# Nikon_PowerBoardV1.net
KiCad netlist of a schematic drawn in EAGLE
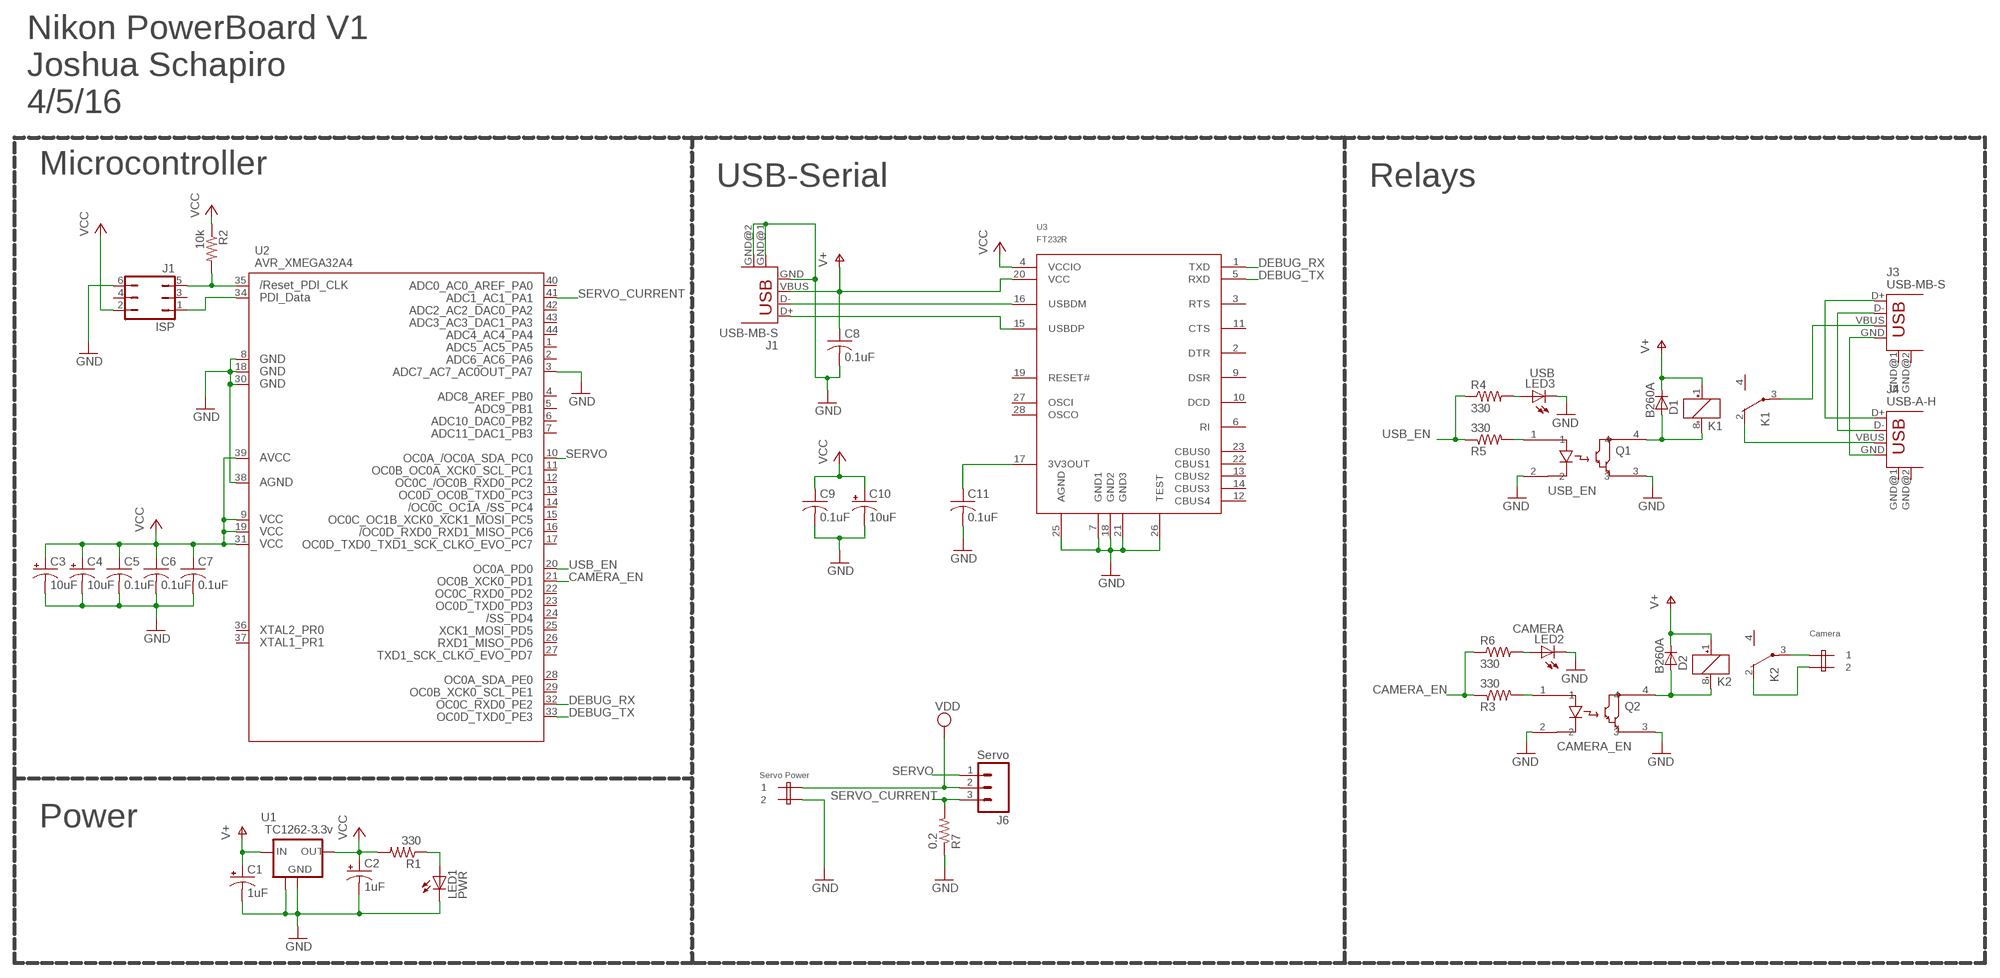
[diagram p0: schematic, sheet 1]

(export (version "E")
  (design (tool "Eeschema 10.0.6"))
  (components
    (comp (ref "C1")
      (value "1uF")
      (footprint "eagle-import:EIA3216")
      (libsource (lib "eagle-import") (part "CAP_POL1206"))
    )
    (comp (ref "C2")
      (value "1uF")
      (footprint "eagle-import:EIA3216")
      (libsource (lib "eagle-import") (part "CAP_POL1206"))
    )
    (comp (ref "C3")
      (value "10uF")
      (footprint "eagle-import:EIA3216")
      (libsource (lib "eagle-import") (part "CAP_POL1206"))
    )
    (comp (ref "C4")
      (value "10uF")
      (footprint "eagle-import:EIA3216")
      (libsource (lib "eagle-import") (part "CAP_POL1206"))
    )
    (comp (ref "C5")
      (value "0.1uF")
      (footprint "eagle-import:C1206")
      (libsource (lib "eagle-import") (part "C-USC1206"))
    )
    (comp (ref "C6")
      (value "0.1uF")
      (footprint "eagle-import:C1206")
      (libsource (lib "eagle-import") (part "C-USC1206"))
    )
    (comp (ref "C7")
      (value "0.1uF")
      (footprint "eagle-import:C1206")
      (libsource (lib "eagle-import") (part "C-USC1206"))
    )
    (comp (ref "C8")
      (value "0.1uF")
      (footprint "eagle-import:C1206")
      (libsource (lib "eagle-import") (part "C-USC1206"))
    )
    (comp (ref "C9")
      (value "0.1uF")
      (footprint "eagle-import:C1206")
      (libsource (lib "eagle-import") (part "C-USC1206"))
    )
    (comp (ref "C10")
      (value "10uF")
      (footprint "eagle-import:EIA3216")
      (libsource (lib "eagle-import") (part "CAP_POL1206"))
    )
    (comp (ref "C11")
      (value "0.1uF")
      (footprint "eagle-import:C1206")
      (libsource (lib "eagle-import") (part "C-USC1206"))
    )
    (comp (ref "D1")
      (value "B260A")
      (footprint "eagle-import:SMA-DIODE")
      (libsource (lib "eagle-import") (part "DIODESMA"))
    )
    (comp (ref "D2")
      (value "B260A")
      (footprint "eagle-import:SMA-DIODE")
      (libsource (lib "eagle-import") (part "DIODESMA"))
    )
    (comp (ref "ISP")
      (value "J1")
      (footprint "eagle-import:JP3Q")
      (libsource (lib "eagle-import") (part "JP3Q"))
    )
    (comp (ref "J1")
      (value "USB-MB-S")
      (footprint "eagle-import:USB-MB-S")
      (libsource (lib "eagle-import") (part "USB-MB-S"))
    )
    (comp (ref "J2")
      (value "Camera")
      (footprint "eagle-import:2-PIN_SCREWTERM")
      (libsource (lib "eagle-import") (part "2-PIN_SCREWTERMINAL"))
    )
    (comp (ref "J3")
      (value "USB-MB-S")
      (footprint "eagle-import:USB-MB-S")
      (libsource (lib "eagle-import") (part "USB-MB-S"))
    )
    (comp (ref "J4")
      (value "USB-A-H")
      (footprint "eagle-import:USB-A-H")
      (libsource (lib "eagle-import") (part "USB-A-H"))
    )
    (comp (ref "J5")
      (value "ServoPower")
      (footprint "eagle-import:2-PIN_SCREWTERM")
      (libsource (lib "eagle-import") (part "2-PIN_SCREWTERMINAL"))
    )
    (comp (ref "J6")
      (value "Servo")
      (footprint "eagle-import:1X03_LONGPADS")
      (libsource (lib "eagle-import") (part "M03LONGPADS"))
    )
    (comp (ref "K1")
      (value "USB_EN")
      (footprint "eagle-import:G6K-2F")
      (libsource (lib "eagle-import") (part "G6K-2F"))
    )
    (comp (ref "K2")
      (value "CAMERA_EN")
      (footprint "eagle-import:G6K-2F")
      (libsource (lib "eagle-import") (part "G6K-2F"))
    )
    (comp (ref "LED1")
      (value "PWR")
      (footprint "eagle-import:CHIPLED_1206")
      (libsource (lib "eagle-import") (part "LEDCHIPLED_1206"))
    )
    (comp (ref "LED2")
      (value "CAMERA")
      (footprint "eagle-import:CHIPLED_1206")
      (libsource (lib "eagle-import") (part "LEDCHIPLED_1206"))
    )
    (comp (ref "LED3")
      (value "USB")
      (footprint "eagle-import:CHIPLED_1206")
      (libsource (lib "eagle-import") (part "LEDCHIPLED_1206"))
    )
    (comp (ref "Q1")
      (value "USB_EN")
      (footprint "eagle-import:4-PIN_MINI-FLAT")
      (libsource (lib "eagle-import") (part "OPTOISOLATOR_SINGLE"))
    )
    (comp (ref "Q2")
      (value "CAMERA_EN")
      (footprint "eagle-import:4-PIN_MINI-FLAT")
      (libsource (lib "eagle-import") (part "OPTOISOLATOR_SINGLE"))
    )
    (comp (ref "R1")
      (value "330")
      (footprint "eagle-import:R1206")
      (libsource (lib "eagle-import") (part "R-US_R1206"))
    )
    (comp (ref "R2")
      (value "10k")
      (footprint "eagle-import:R1206")
      (libsource (lib "eagle-import") (part "R-US_R1206"))
    )
    (comp (ref "R3")
      (value "330")
      (footprint "eagle-import:R1206")
      (libsource (lib "eagle-import") (part "R-US_R1206"))
    )
    (comp (ref "R4")
      (value "330")
      (footprint "eagle-import:R1206")
      (libsource (lib "eagle-import") (part "R-US_R1206"))
    )
    (comp (ref "R5")
      (value "330")
      (footprint "eagle-import:R1206")
      (libsource (lib "eagle-import") (part "R-US_R1206"))
    )
    (comp (ref "R6")
      (value "330")
      (footprint "eagle-import:R1206")
      (libsource (lib "eagle-import") (part "R-US_R1206"))
    )
    (comp (ref "R7")
      (value "0.2")
      (footprint "eagle-import:R1206")
      (libsource (lib "eagle-import") (part "R-US_R1206"))
    )
    (comp (ref "U1")
      (value "TC1262-3.3v")
      (footprint "eagle-import:SOT223")
      (libsource (lib "eagle-import") (part "REGULATOR"))
    )
    (comp (ref "U2")
      (value "AVR_XMEGA32A4")
      (footprint "eagle-import:TQFP44")
      (libsource (lib "eagle-import") (part "AVR_XMEGA_A4_44A"))
    )
    (comp (ref "U3")
      (value "FT232R")
      (footprint "eagle-import:SSOP28")
      (libsource (lib "eagle-import") (part "FT232R"))
    )
  )
  (nets
    (net (code "1") (name "/CAMERA_EN") (class "Default")
      (node (ref "R3") (pin "1") (pinfunction "1_1") (pintype "passive"))
      (node (ref "R6") (pin "1") (pinfunction "1_1") (pintype "passive"))
      (node (ref "U2") (pin "21") (pinfunction "PD1_21") (pintype "bidirectional"))
    )
    (net (code "2") (name "/DEBUG_RX") (class "Default")
      (node (ref "U2") (pin "32") (pinfunction "PE2_32") (pintype "bidirectional"))
      (node (ref "U3") (pin "1") (pinfunction "TXD_1") (pintype "bidirectional"))
    )
    (net (code "3") (name "/DEBUG_TX") (class "Default")
      (node (ref "U2") (pin "33") (pinfunction "PE3_33") (pintype "bidirectional"))
      (node (ref "U3") (pin "5") (pinfunction "RXD_5") (pintype "bidirectional"))
    )
    (net (code "4") (name "/SERVO") (class "Default")
      (node (ref "J6") (pin "1") (pinfunction "1_1") (pintype "passive"))
      (node (ref "U2") (pin "10") (pinfunction "PC0_10") (pintype "bidirectional"))
    )
    (net (code "5") (name "/SERVO_CURRENT") (class "Default")
      (node (ref "J6") (pin "3") (pinfunction "3_3") (pintype "passive"))
      (node (ref "R7") (pin "2") (pinfunction "2_2") (pintype "passive"))
      (node (ref "U2") (pin "41") (pinfunction "PA1_41") (pintype "bidirectional"))
    )
    (net (code "6") (name "/USB_EN") (class "Default")
      (node (ref "R4") (pin "1") (pinfunction "1_1") (pintype "passive"))
      (node (ref "R5") (pin "1") (pinfunction "1_1") (pintype "passive"))
      (node (ref "U2") (pin "20") (pinfunction "PD0_20") (pintype "bidirectional"))
    )
    (net (code "7") (name "GND") (class "Default")
      (node (ref "C1") (pin "C") (pinfunction "-_C") (pintype "passive"))
      (node (ref "C10") (pin "C") (pinfunction "-_C") (pintype "passive"))
      (node (ref "C11") (pin "2") (pinfunction "2_2") (pintype "passive"))
      (node (ref "C2") (pin "C") (pinfunction "-_C") (pintype "passive"))
      (node (ref "C3") (pin "C") (pinfunction "-_C") (pintype "passive"))
      (node (ref "C4") (pin "C") (pinfunction "-_C") (pintype "passive"))
      (node (ref "C5") (pin "2") (pinfunction "2_2") (pintype "passive"))
      (node (ref "C6") (pin "2") (pinfunction "2_2") (pintype "passive"))
      (node (ref "C7") (pin "2") (pinfunction "2_2") (pintype "passive"))
      (node (ref "C8") (pin "2") (pinfunction "2_2") (pintype "passive"))
      (node (ref "C9") (pin "2") (pinfunction "2_2") (pintype "passive"))
      (node (ref "ISP") (pin "6") (pinfunction "6_6") (pintype "passive"))
      (node (ref "J1") (pin "GND") (pinfunction "GND_GND") (pintype "bidirectional"))
      (node (ref "J1") (pin "GND@1") (pinfunction "GND_GND@1") (pintype "bidirectional"))
      (node (ref "J1") (pin "GND@2") (pinfunction "GND_GND@2") (pintype "bidirectional"))
      (node (ref "J5") (pin "P$2") (pinfunction "2_P$2") (pintype "bidirectional"))
      (node (ref "LED1") (pin "C") (pinfunction "C_C") (pintype "passive"))
      (node (ref "LED2") (pin "C") (pinfunction "C_C") (pintype "passive"))
      (node (ref "LED3") (pin "C") (pinfunction "C_C") (pintype "passive"))
      (node (ref "Q1") (pin "2") (pinfunction "2_2") (pintype "bidirectional"))
      (node (ref "Q1") (pin "3") (pinfunction "3_3") (pintype "bidirectional"))
      (node (ref "Q2") (pin "2") (pinfunction "2_2") (pintype "bidirectional"))
      (node (ref "Q2") (pin "3") (pinfunction "3_3") (pintype "bidirectional"))
      (node (ref "R7") (pin "1") (pinfunction "1_1") (pintype "passive"))
      (node (ref "U1") (pin "2") (pinfunction "GND_2") (pintype "bidirectional"))
      (node (ref "U1") (pin "4") (pinfunction "GND1_4") (pintype "bidirectional"))
      (node (ref "U2") (pin "18") (pinfunction "GND2_18") (pintype "bidirectional"))
      (node (ref "U2") (pin "3") (pinfunction "PA7_3") (pintype "bidirectional"))
      (node (ref "U2") (pin "30") (pinfunction "GND3_30") (pintype "bidirectional"))
      (node (ref "U2") (pin "38") (pinfunction "AGND_38") (pintype "bidirectional"))
      (node (ref "U2") (pin "8") (pinfunction "GND1_8") (pintype "bidirectional"))
      (node (ref "U3") (pin "18") (pinfunction "GND2_18") (pintype "bidirectional"))
      (node (ref "U3") (pin "21") (pinfunction "GND3_21") (pintype "bidirectional"))
      (node (ref "U3") (pin "25") (pinfunction "AGND_25") (pintype "bidirectional"))
      (node (ref "U3") (pin "26") (pinfunction "TEST_26") (pintype "bidirectional"))
      (node (ref "U3") (pin "7") (pinfunction "GND1_7") (pintype "bidirectional"))
    )
    (net (code "8") (name "Net-(J2-1)") (class "Default")
      (node (ref "J2") (pin "P$1") (pinfunction "1_P$1") (pintype "bidirectional"))
      (node (ref "K2") (pin "3") (pinfunction "P_3") (pintype "passive"))
    )
    (net (code "9") (name "Net-(J2-2)") (class "Default")
      (node (ref "J2") (pin "P$2") (pinfunction "2_P$2") (pintype "bidirectional"))
      (node (ref "K2") (pin "2") (pinfunction "O_2") (pintype "passive"))
    )
    (net (code "10") (name "Net-(J3-PadD+)") (class "Default")
      (node (ref "J3") (pin "D+") (pinfunction "D+_D+") (pintype "bidirectional"))
      (node (ref "J4") (pin "D+") (pinfunction "D+_D+") (pintype "bidirectional"))
    )
    (net (code "11") (name "Net-(J3-PadD-)") (class "Default")
      (node (ref "J3") (pin "D-") (pinfunction "D-_D-") (pintype "bidirectional"))
      (node (ref "J4") (pin "D-") (pinfunction "D-_D-") (pintype "bidirectional"))
    )
    (net (code "12") (name "Net-(J3-PadGND)") (class "Default")
      (node (ref "J3") (pin "GND") (pinfunction "GND_GND") (pintype "bidirectional"))
      (node (ref "J4") (pin "GND") (pinfunction "GND_GND") (pintype "bidirectional"))
    )
    (net (code "13") (name "Net-(K1A--)") (class "Default")
      (node (ref "D1") (pin "A") (pinfunction "A_A") (pintype "passive"))
      (node (ref "K1") (pin "8") (pinfunction "-_8") (pintype "passive"))
      (node (ref "Q1") (pin "4") (pinfunction "4_4") (pintype "bidirectional"))
    )
    (net (code "14") (name "Net-(K1B-O)") (class "Default")
      (node (ref "J4") (pin "VBUS") (pinfunction "VBUS_VBUS") (pintype "bidirectional"))
      (node (ref "K1") (pin "2") (pinfunction "O_2") (pintype "passive"))
    )
    (net (code "15") (name "Net-(K1B-P)") (class "Default")
      (node (ref "J3") (pin "VBUS") (pinfunction "VBUS_VBUS") (pintype "bidirectional"))
      (node (ref "K1") (pin "3") (pinfunction "P_3") (pintype "passive"))
    )
    (net (code "16") (name "Net-(K2A--)") (class "Default")
      (node (ref "D2") (pin "A") (pinfunction "A_A") (pintype "passive"))
      (node (ref "K2") (pin "8") (pinfunction "-_8") (pintype "passive"))
      (node (ref "Q2") (pin "4") (pinfunction "4_4") (pintype "bidirectional"))
    )
    (net (code "17") (name "Net-(LED1-PadA)") (class "Default")
      (node (ref "LED1") (pin "A") (pinfunction "A_A") (pintype "passive"))
      (node (ref "R1") (pin "1") (pinfunction "1_1") (pintype "passive"))
    )
    (net (code "18") (name "Net-(LED2-PadA)") (class "Default")
      (node (ref "LED2") (pin "A") (pinfunction "A_A") (pintype "passive"))
      (node (ref "R6") (pin "2") (pinfunction "2_2") (pintype "passive"))
    )
    (net (code "19") (name "Net-(LED3-PadA)") (class "Default")
      (node (ref "LED3") (pin "A") (pinfunction "A_A") (pintype "passive"))
      (node (ref "R4") (pin "2") (pinfunction "2_2") (pintype "passive"))
    )
    (net (code "20") (name "Net-(Q1-Pad1)") (class "Default")
      (node (ref "Q1") (pin "1") (pinfunction "1_1") (pintype "bidirectional"))
      (node (ref "R5") (pin "2") (pinfunction "2_2") (pintype "passive"))
    )
    (net (code "21") (name "Net-(Q2-Pad1)") (class "Default")
      (node (ref "Q2") (pin "1") (pinfunction "1_1") (pintype "bidirectional"))
      (node (ref "R3") (pin "2") (pinfunction "2_2") (pintype "passive"))
    )
    (net (code "22") (name "Net-(U2-PDI_DATA)") (class "Default")
      (node (ref "ISP") (pin "1") (pinfunction "1_1") (pintype "passive"))
      (node (ref "U2") (pin "34") (pinfunction "PDI_DATA_34") (pintype "bidirectional"))
    )
    (net (code "23") (name "Net-(U2-RESET)") (class "Default")
      (node (ref "ISP") (pin "5") (pinfunction "5_5") (pintype "passive"))
      (node (ref "R2") (pin "2") (pinfunction "2_2") (pintype "passive"))
      (node (ref "U2") (pin "35") (pinfunction "RESET_35") (pintype "bidirectional"))
    )
    (net (code "24") (name "Net-(U3-3V3OUT)") (class "Default")
      (node (ref "C11") (pin "1") (pinfunction "1_1") (pintype "passive"))
      (node (ref "U3") (pin "17") (pinfunction "3V3OUT_17") (pintype "bidirectional"))
    )
    (net (code "25") (name "Net-(U3-USBDM)") (class "Default")
      (node (ref "J1") (pin "D-") (pinfunction "D-_D-") (pintype "bidirectional"))
      (node (ref "U3") (pin "16") (pinfunction "USBDM_16") (pintype "bidirectional"))
    )
    (net (code "26") (name "Net-(U3-USBDP)") (class "Default")
      (node (ref "J1") (pin "D+") (pinfunction "D+_D+") (pintype "bidirectional"))
      (node (ref "U3") (pin "15") (pinfunction "USBDP_15") (pintype "bidirectional"))
    )
    (net (code "27") (name "V+") (class "Default")
      (node (ref "C1") (pin "A") (pinfunction "+_A") (pintype "passive"))
      (node (ref "C8") (pin "1") (pinfunction "1_1") (pintype "passive"))
      (node (ref "D1") (pin "C") (pinfunction "C_C") (pintype "passive"))
      (node (ref "D2") (pin "C") (pinfunction "C_C") (pintype "passive"))
      (node (ref "J1") (pin "VBUS") (pinfunction "VBUS_VBUS") (pintype "bidirectional"))
      (node (ref "K1") (pin "1") (pinfunction "+_1") (pintype "passive"))
      (node (ref "K2") (pin "1") (pinfunction "+_1") (pintype "passive"))
      (node (ref "U1") (pin "1") (pinfunction "IN_1") (pintype "bidirectional"))
      (node (ref "U3") (pin "20") (pinfunction "VCC_20") (pintype "bidirectional"))
    )
    (net (code "28") (name "VCC") (class "Default")
      (node (ref "C10") (pin "A") (pinfunction "+_A") (pintype "passive"))
      (node (ref "C2") (pin "A") (pinfunction "+_A") (pintype "passive"))
      (node (ref "C3") (pin "A") (pinfunction "+_A") (pintype "passive"))
      (node (ref "C4") (pin "A") (pinfunction "+_A") (pintype "passive"))
      (node (ref "C5") (pin "1") (pinfunction "1_1") (pintype "passive"))
      (node (ref "C6") (pin "1") (pinfunction "1_1") (pintype "passive"))
      (node (ref "C7") (pin "1") (pinfunction "1_1") (pintype "passive"))
      (node (ref "C9") (pin "1") (pinfunction "1_1") (pintype "passive"))
      (node (ref "ISP") (pin "2") (pinfunction "2_2") (pintype "passive"))
      (node (ref "R1") (pin "2") (pinfunction "2_2") (pintype "passive"))
      (node (ref "R2") (pin "1") (pinfunction "1_1") (pintype "passive"))
      (node (ref "U1") (pin "3") (pinfunction "OUT_3") (pintype "bidirectional"))
      (node (ref "U2") (pin "19") (pinfunction "VCC2_19") (pintype "bidirectional"))
      (node (ref "U2") (pin "31") (pinfunction "VCC3_31") (pintype "bidirectional"))
      (node (ref "U2") (pin "39") (pinfunction "AVCC_39") (pintype "bidirectional"))
      (node (ref "U2") (pin "9") (pinfunction "VCC1_9") (pintype "bidirectional"))
      (node (ref "U3") (pin "4") (pinfunction "VCCIO_4") (pintype "bidirectional"))
    )
    (net (code "29") (name "VDD") (class "Default")
      (node (ref "J5") (pin "P$1") (pinfunction "1_P$1") (pintype "bidirectional"))
      (node (ref "J6") (pin "2") (pinfunction "2_2") (pintype "passive"))
    )
    (net (code "30") (name "unconnected-(ISP-Pad3)") (class "Default")
      (node (ref "ISP") (pin "3") (pinfunction "3_3") (pintype "passive"))
    )
    (net (code "31") (name "unconnected-(ISP-Pad4)") (class "Default")
      (node (ref "ISP") (pin "4") (pinfunction "4_4") (pintype "passive"))
    )
    (net (code "32") (name "unconnected-(J3-GND-PadGND@1)") (class "Default")
      (node (ref "J3") (pin "GND@1") (pinfunction "GND_GND@1") (pintype "bidirectional"))
    )
    (net (code "33") (name "unconnected-(J3-GND-PadGND@2)") (class "Default")
      (node (ref "J3") (pin "GND@2") (pinfunction "GND_GND@2") (pintype "bidirectional"))
    )
    (net (code "34") (name "unconnected-(J4-GND-PadGND@1)") (class "Default")
      (node (ref "J4") (pin "GND@1") (pinfunction "GND_GND@1") (pintype "bidirectional"))
    )
    (net (code "35") (name "unconnected-(J4-GND-PadGND@2)") (class "Default")
      (node (ref "J4") (pin "GND@2") (pinfunction "GND_GND@2") (pintype "bidirectional"))
    )
    (net (code "36") (name "unconnected-(K1B-S-Pad4)") (class "Default")
      (node (ref "K1") (pin "4") (pinfunction "S_4") (pintype "passive"))
    )
    (net (code "37") (name "unconnected-(K2B-S-Pad4)") (class "Default")
      (node (ref "K2") (pin "4") (pinfunction "S_4") (pintype "passive"))
    )
    (net (code "38") (name "unconnected-(U2-PA0-Pad40)") (class "Default")
      (node (ref "U2") (pin "40") (pinfunction "PA0_40") (pintype "bidirectional"))
    )
    (net (code "39") (name "unconnected-(U2-PA2-Pad42)") (class "Default")
      (node (ref "U2") (pin "42") (pinfunction "PA2_42") (pintype "bidirectional"))
    )
    (net (code "40") (name "unconnected-(U2-PA3-Pad43)") (class "Default")
      (node (ref "U2") (pin "43") (pinfunction "PA3_43") (pintype "bidirectional"))
    )
    (net (code "41") (name "unconnected-(U2-PA4-Pad44)") (class "Default")
      (node (ref "U2") (pin "44") (pinfunction "PA4_44") (pintype "bidirectional"))
    )
    (net (code "42") (name "unconnected-(U2-PA5-Pad1)") (class "Default")
      (node (ref "U2") (pin "1") (pinfunction "PA5_1") (pintype "bidirectional"))
    )
    (net (code "43") (name "unconnected-(U2-PA6-Pad2)") (class "Default")
      (node (ref "U2") (pin "2") (pinfunction "PA6_2") (pintype "bidirectional"))
    )
    (net (code "44") (name "unconnected-(U2-PB0-Pad4)") (class "Default")
      (node (ref "U2") (pin "4") (pinfunction "PB0_4") (pintype "bidirectional"))
    )
    (net (code "45") (name "unconnected-(U2-PB1-Pad5)") (class "Default")
      (node (ref "U2") (pin "5") (pinfunction "PB1_5") (pintype "bidirectional"))
    )
    (net (code "46") (name "unconnected-(U2-PB2-Pad6)") (class "Default")
      (node (ref "U2") (pin "6") (pinfunction "PB2_6") (pintype "bidirectional"))
    )
    (net (code "47") (name "unconnected-(U2-PB3-Pad7)") (class "Default")
      (node (ref "U2") (pin "7") (pinfunction "PB3_7") (pintype "bidirectional"))
    )
    (net (code "48") (name "unconnected-(U2-PC1-Pad11)") (class "Default")
      (node (ref "U2") (pin "11") (pinfunction "PC1_11") (pintype "bidirectional"))
    )
    (net (code "49") (name "unconnected-(U2-PC2-Pad12)") (class "Default")
      (node (ref "U2") (pin "12") (pinfunction "PC2_12") (pintype "bidirectional"))
    )
    (net (code "50") (name "unconnected-(U2-PC3-Pad13)") (class "Default")
      (node (ref "U2") (pin "13") (pinfunction "PC3_13") (pintype "bidirectional"))
    )
    (net (code "51") (name "unconnected-(U2-PC4-Pad14)") (class "Default")
      (node (ref "U2") (pin "14") (pinfunction "PC4_14") (pintype "bidirectional"))
    )
    (net (code "52") (name "unconnected-(U2-PC5-Pad15)") (class "Default")
      (node (ref "U2") (pin "15") (pinfunction "PC5_15") (pintype "bidirectional"))
    )
    (net (code "53") (name "unconnected-(U2-PC6-Pad16)") (class "Default")
      (node (ref "U2") (pin "16") (pinfunction "PC6_16") (pintype "bidirectional"))
    )
    (net (code "54") (name "unconnected-(U2-PC7-Pad17)") (class "Default")
      (node (ref "U2") (pin "17") (pinfunction "PC7_17") (pintype "bidirectional"))
    )
    (net (code "55") (name "unconnected-(U2-PD2-Pad22)") (class "Default")
      (node (ref "U2") (pin "22") (pinfunction "PD2_22") (pintype "bidirectional"))
    )
    (net (code "56") (name "unconnected-(U2-PD3-Pad23)") (class "Default")
      (node (ref "U2") (pin "23") (pinfunction "PD3_23") (pintype "bidirectional"))
    )
    (net (code "57") (name "unconnected-(U2-PD4-Pad24)") (class "Default")
      (node (ref "U2") (pin "24") (pinfunction "PD4_24") (pintype "bidirectional"))
    )
    (net (code "58") (name "unconnected-(U2-PD5-Pad25)") (class "Default")
      (node (ref "U2") (pin "25") (pinfunction "PD5_25") (pintype "bidirectional"))
    )
    (net (code "59") (name "unconnected-(U2-PD6-Pad26)") (class "Default")
      (node (ref "U2") (pin "26") (pinfunction "PD6_26") (pintype "bidirectional"))
    )
    (net (code "60") (name "unconnected-(U2-PD7-Pad27)") (class "Default")
      (node (ref "U2") (pin "27") (pinfunction "PD7_27") (pintype "bidirectional"))
    )
    (net (code "61") (name "unconnected-(U2-PE0-Pad28)") (class "Default")
      (node (ref "U2") (pin "28") (pinfunction "PE0_28") (pintype "bidirectional"))
    )
    (net (code "62") (name "unconnected-(U2-PE1-Pad29)") (class "Default")
      (node (ref "U2") (pin "29") (pinfunction "PE1_29") (pintype "bidirectional"))
    )
    (net (code "63") (name "unconnected-(U2-PR0-Pad36)") (class "Default")
      (node (ref "U2") (pin "36") (pinfunction "PR0_36") (pintype "bidirectional"))
    )
    (net (code "64") (name "unconnected-(U2-PR1-Pad37)") (class "Default")
      (node (ref "U2") (pin "37") (pinfunction "PR1_37") (pintype "bidirectional"))
    )
    (net (code "65") (name "unconnected-(U3-CBUS0-Pad23)") (class "Default")
      (node (ref "U3") (pin "23") (pinfunction "CBUS0_23") (pintype "bidirectional"))
    )
    (net (code "66") (name "unconnected-(U3-CBUS1-Pad22)") (class "Default")
      (node (ref "U3") (pin "22") (pinfunction "CBUS1_22") (pintype "bidirectional"))
    )
    (net (code "67") (name "unconnected-(U3-CBUS2-Pad13)") (class "Default")
      (node (ref "U3") (pin "13") (pinfunction "CBUS2_13") (pintype "bidirectional"))
    )
    (net (code "68") (name "unconnected-(U3-CBUS3-Pad14)") (class "Default")
      (node (ref "U3") (pin "14") (pinfunction "CBUS3_14") (pintype "bidirectional"))
    )
    (net (code "69") (name "unconnected-(U3-CBUS4-Pad12)") (class "Default")
      (node (ref "U3") (pin "12") (pinfunction "CBUS4_12") (pintype "bidirectional"))
    )
    (net (code "70") (name "unconnected-(U3-CTS-Pad11)") (class "Default")
      (node (ref "U3") (pin "11") (pinfunction "CTS_11") (pintype "bidirectional"))
    )
    (net (code "71") (name "unconnected-(U3-DCD-Pad10)") (class "Default")
      (node (ref "U3") (pin "10") (pinfunction "DCD_10") (pintype "bidirectional"))
    )
    (net (code "72") (name "unconnected-(U3-DSR-Pad9)") (class "Default")
      (node (ref "U3") (pin "9") (pinfunction "DSR_9") (pintype "bidirectional"))
    )
    (net (code "73") (name "unconnected-(U3-DTR-Pad2)") (class "Default")
      (node (ref "U3") (pin "2") (pinfunction "DTR_2") (pintype "bidirectional"))
    )
    (net (code "74") (name "unconnected-(U3-OSCI-Pad27)") (class "Default")
      (node (ref "U3") (pin "27") (pinfunction "OSCI_27") (pintype "bidirectional"))
    )
    (net (code "75") (name "unconnected-(U3-OSCO-Pad28)") (class "Default")
      (node (ref "U3") (pin "28") (pinfunction "OSCO_28") (pintype "bidirectional"))
    )
    (net (code "76") (name "unconnected-(U3-RESET#-Pad19)") (class "Default")
      (node (ref "U3") (pin "19") (pinfunction "RESET#_19") (pintype "bidirectional"))
    )
    (net (code "77") (name "unconnected-(U3-RI-Pad6)") (class "Default")
      (node (ref "U3") (pin "6") (pinfunction "RI_6") (pintype "bidirectional"))
    )
    (net (code "78") (name "unconnected-(U3-RTS-Pad3)") (class "Default")
      (node (ref "U3") (pin "3") (pinfunction "RTS_3") (pintype "bidirectional"))
    )
  )
)
